# BUCK-BOOST_DC-DC_old.net
KiCad netlist of a schematic drawn in Altium Designer
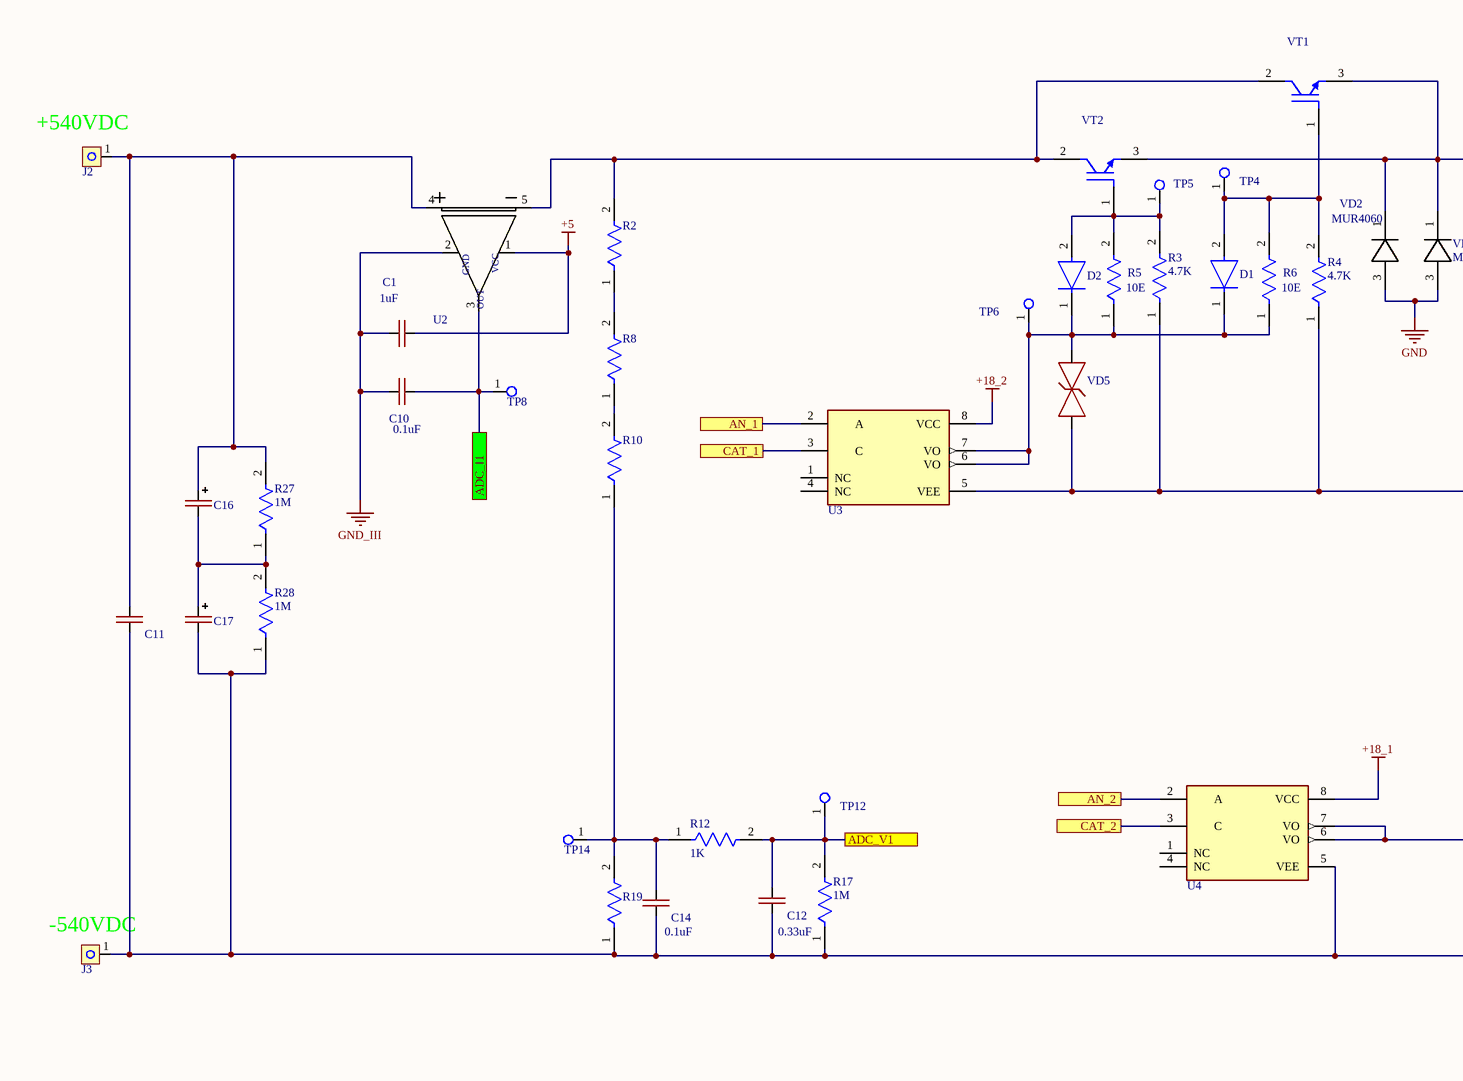
[diagram p0: BUCK-BOOST_DC-DC_old.SchDoc, top left]
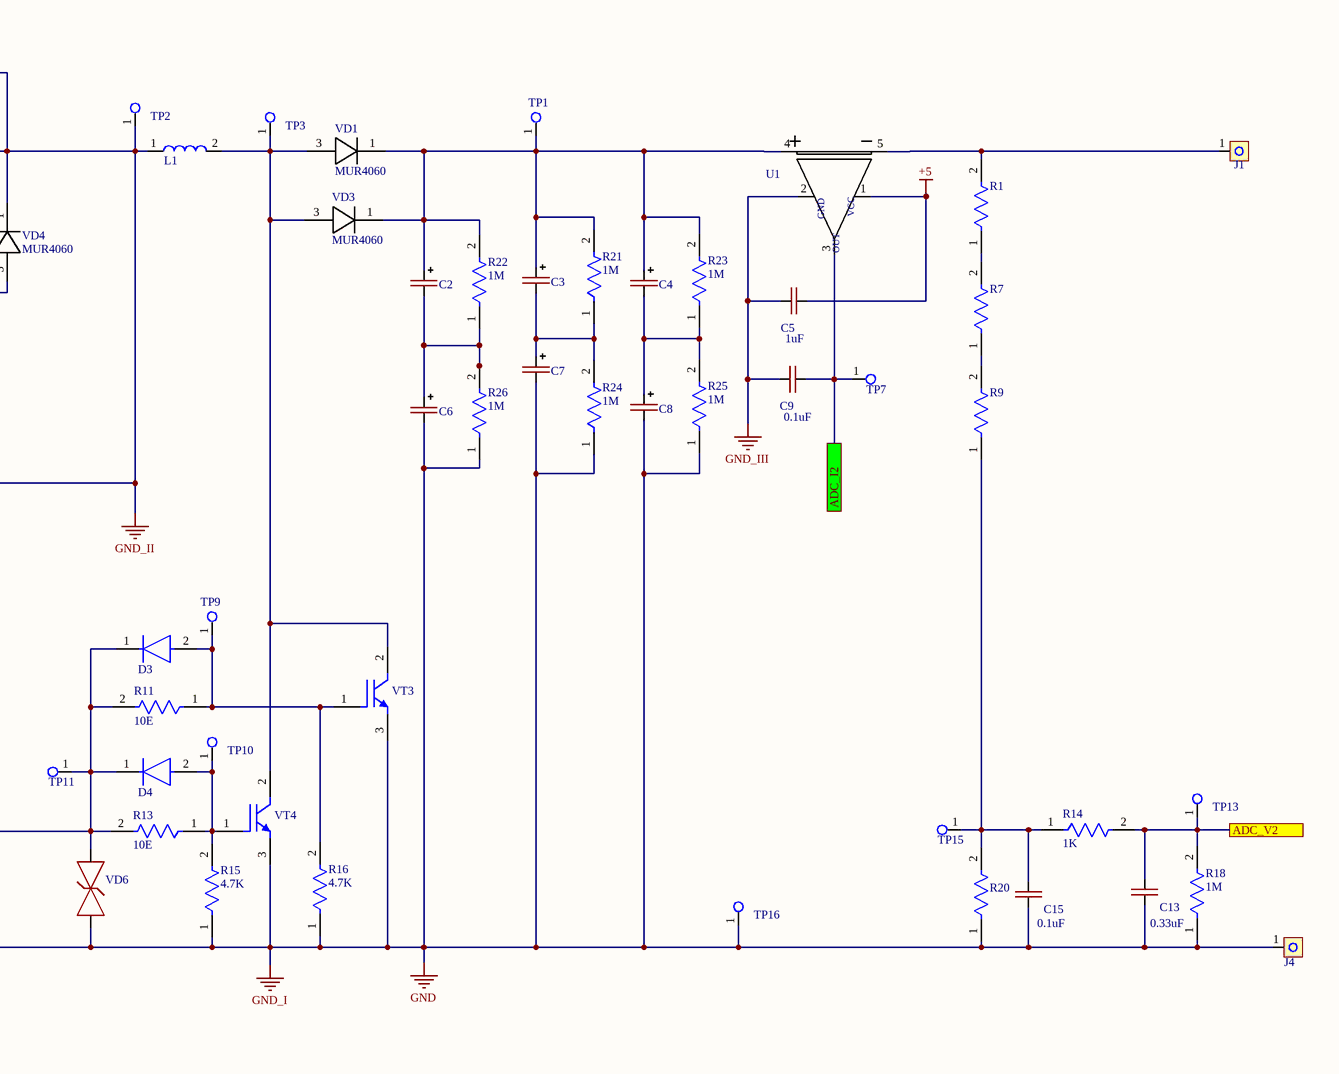
[diagram p1: BUCK-BOOST_DC-DC_old.SchDoc, top right]
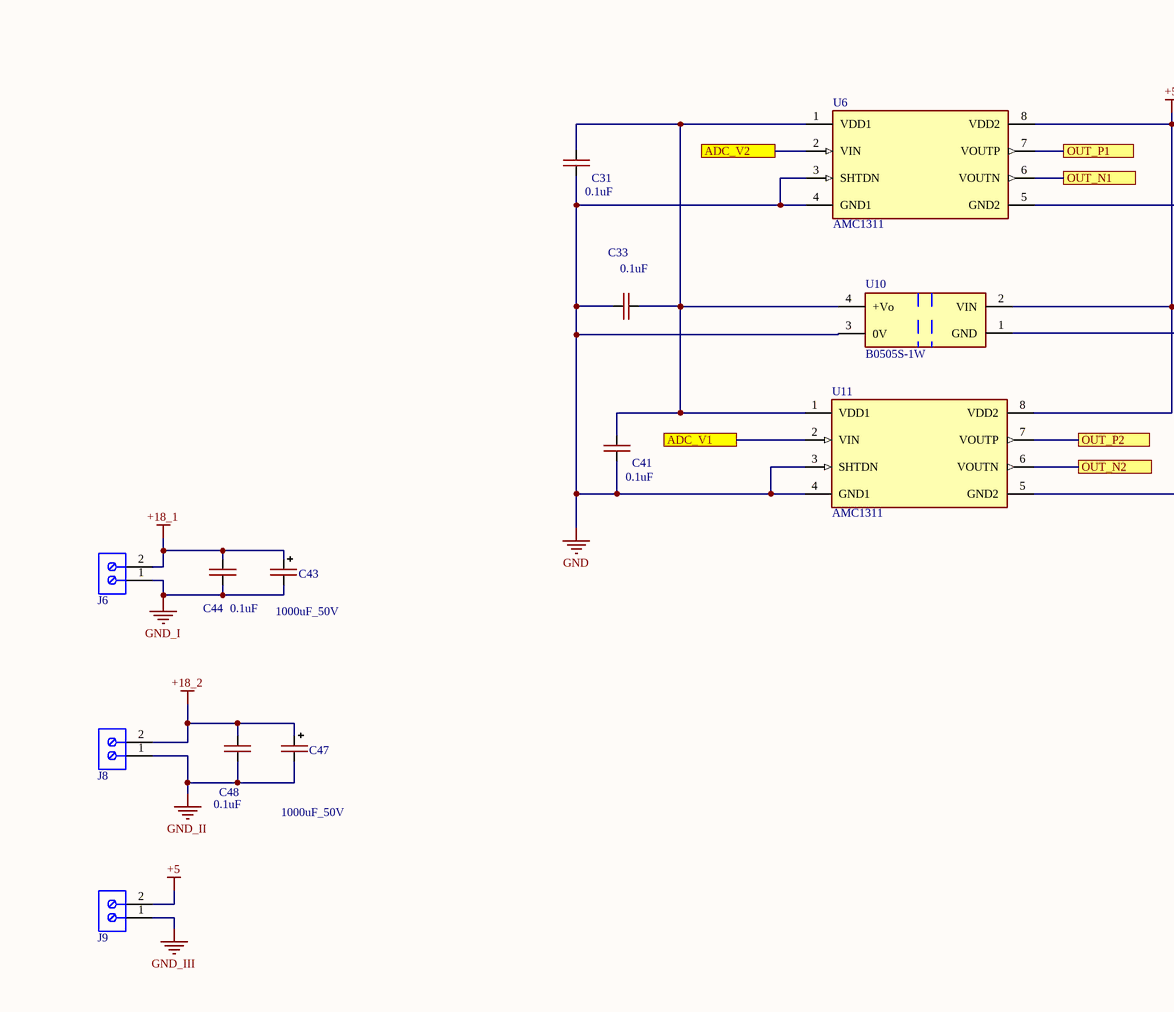
[diagram p2: BUCK-BOOST_DC-DC_old.SchDoc, bottom left]
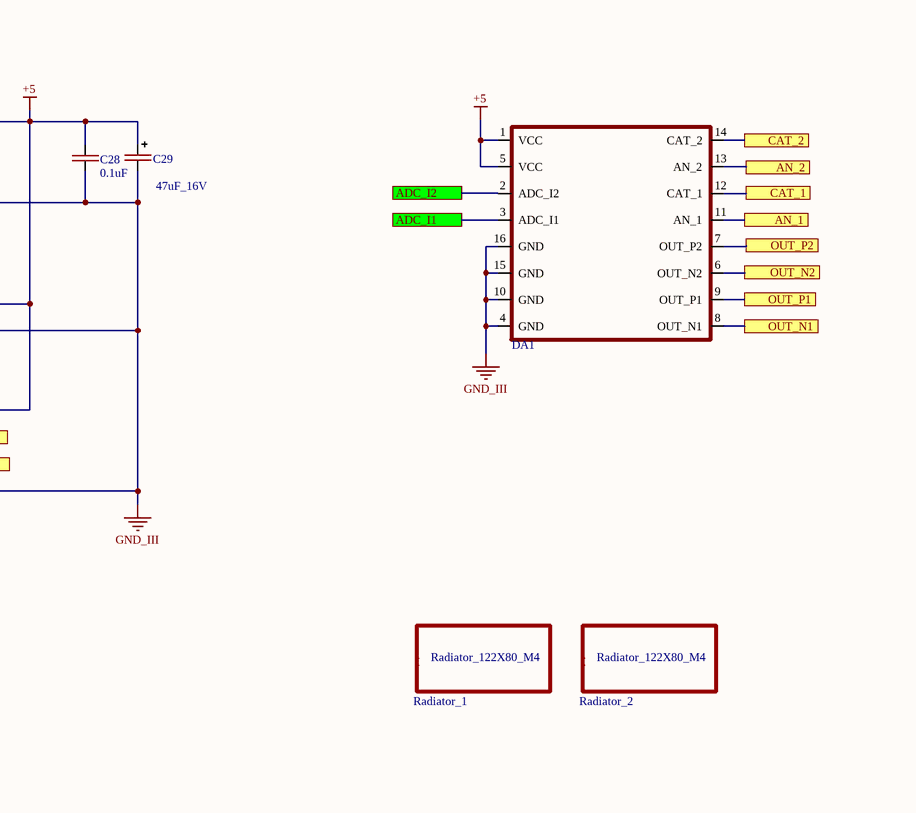
[diagram p3: BUCK-BOOST_DC-DC_old.SchDoc, bottom right]

(export (version "E")
  (design (tool "Eeschema 10.0.6"))
  (components
    (comp (ref "C1")
      (value "1uF")
      (footprint "CAP-0805")
      (libsource (lib "PASSIVE_COMPONENTS") (part "CAP-NON-POLAR"))
    )
    (comp (ref "C2")
      (value "CAP-POLAR")
      (footprint "CAP 100uF_500V 22x40mm")
      (libsource (lib "PASSIVE_COMPONENTS") (part "CAP-POLAR"))
    )
    (comp (ref "C3")
      (value "CAP-POLAR")
      (footprint "CAP 100uF_500V 22x40mm")
      (libsource (lib "PASSIVE_COMPONENTS") (part "CAP-POLAR"))
    )
    (comp (ref "C4")
      (value "CAP-POLAR")
      (footprint "CAP 100uF_500V 22x40mm")
      (libsource (lib "PASSIVE_COMPONENTS") (part "CAP-POLAR"))
    )
    (comp (ref "C5")
      (value "1uF")
      (footprint "CAP-0805")
      (libsource (lib "PASSIVE_COMPONENTS") (part "CAP-NON-POLAR"))
    )
    (comp (ref "C6")
      (value "CAP-POLAR")
      (footprint "CAP 100uF_500V 22x40mm")
      (libsource (lib "PASSIVE_COMPONENTS") (part "CAP-POLAR"))
    )
    (comp (ref "C7")
      (value "CAP-POLAR")
      (footprint "CAP 100uF_500V 22x40mm")
      (libsource (lib "PASSIVE_COMPONENTS") (part "CAP-POLAR"))
    )
    (comp (ref "C8")
      (value "CAP-POLAR")
      (footprint "CAP 100uF_500V 22x40mm")
      (libsource (lib "PASSIVE_COMPONENTS") (part "CAP-POLAR"))
    )
    (comp (ref "C9")
      (value "0.1uF")
      (footprint "CAP-0805")
      (libsource (lib "PASSIVE_COMPONENTS") (part "CAP-NON-POLAR"))
    )
    (comp (ref "C10")
      (value "0.1uF")
      (footprint "CAP-0805")
      (libsource (lib "PASSIVE_COMPONENTS") (part "CAP-NON-POLAR"))
    )
    (comp (ref "C11")
      (value "CAP-NON-POLAR")
      (footprint "CAP_4.7uF_630V")
      (libsource (lib "PASSIVE_COMPONENTS") (part "CAP-NON-POLAR"))
    )
    (comp (ref "C12")
      (value "0.33uF")
      (footprint "CAP-0805")
      (libsource (lib "PASSIVE_COMPONENTS") (part "CAP-NON-POLAR"))
    )
    (comp (ref "C13")
      (value "0.33uF")
      (footprint "CAP-0805")
      (libsource (lib "PASSIVE_COMPONENTS") (part "CAP-NON-POLAR"))
    )
    (comp (ref "C14")
      (value "0.1uF")
      (footprint "CAP-0805")
      (libsource (lib "PASSIVE_COMPONENTS") (part "CAP-NON-POLAR"))
    )
    (comp (ref "C15")
      (value "0.1uF")
      (footprint "CAP-0805")
      (libsource (lib "PASSIVE_COMPONENTS") (part "CAP-NON-POLAR"))
    )
    (comp (ref "C16")
      (value "CAP-POLAR")
      (footprint "CAP_POL_36X60")
      (libsource (lib "PASSIVE_COMPONENTS") (part "CAP-POLAR"))
    )
    (comp (ref "C17")
      (value "CAP-POLAR")
      (footprint "CAP_POL_36X60")
      (libsource (lib "PASSIVE_COMPONENTS") (part "CAP-POLAR"))
    )
    (comp (ref "C28")
      (value "0.1uF")
      (footprint "CAP-0805")
      (libsource (lib "PASSIVE_COMPONENTS") (part "CAP-NON-POLAR"))
    )
    (comp (ref "C29")
      (value "47uF_16V")
      (footprint "CAP-TAN-D")
      (libsource (lib "PASSIVE_COMPONENTS") (part "CAP-POLAR"))
    )
    (comp (ref "C31")
      (value "0.1uF")
      (footprint "CAP-0805")
      (libsource (lib "PASSIVE_COMPONENTS") (part "CAP-NON-POLAR"))
    )
    (comp (ref "C33")
      (value "0.1uF")
      (footprint "CAP-0805")
      (libsource (lib "PASSIVE_COMPONENTS") (part "CAP-NON-POLAR"))
    )
    (comp (ref "C41")
      (value "0.1uF")
      (footprint "CAP-0805")
      (libsource (lib "PASSIVE_COMPONENTS") (part "CAP-NON-POLAR"))
    )
    (comp (ref "C43")
      (value "1000uF_50V")
      (footprint "CAPPOL-16x25")
      (libsource (lib "PASSIVE_COMPONENTS") (part "CAP-POLAR"))
    )
    (comp (ref "C44")
      (value "0.1uF")
      (footprint "CAP-0805")
      (libsource (lib "PASSIVE_COMPONENTS") (part "CAP-NON-POLAR"))
    )
    (comp (ref "C47")
      (value "1000uF_50V")
      (footprint "CAPPOL-16x25")
      (libsource (lib "PASSIVE_COMPONENTS") (part "CAP-POLAR"))
    )
    (comp (ref "C48")
      (value "0.1uF")
      (footprint "CAP-0805")
      (libsource (lib "PASSIVE_COMPONENTS") (part "CAP-NON-POLAR"))
    )
    (comp (ref "D1") (value "US1G") (footprint "DO-214AA") (libsource (lib "Diodes") (part "US1G")))
    (comp (ref "D2") (value "US1G") (footprint "DO-214AA") (libsource (lib "Diodes") (part "US1G")))
    (comp (ref "D3") (value "US1G") (footprint "DO-214AA") (libsource (lib "Diodes") (part "US1G")))
    (comp (ref "D4") (value "US1G") (footprint "DO-214AA") (libsource (lib "Diodes") (part "US1G")))
    (comp (ref "DA1")
      (value "BOARD_PFC")
      (footprint "BOARD_PFC")
      (libsource (lib "BOARD_PFC") (part "BOARD_PFC"))
    )
    (comp (ref "J1")
      (value "MG_136_HT")
      (footprint "Conn_MEIGAN_MG136HT")
      (libsource (lib "Connectors") (part "Connector_MEIGAN_MG136HT"))
    )
    (comp (ref "J2")
      (value "MG_136_HT")
      (footprint "Conn_MEIGAN_MG136HT")
      (libsource (lib "") (part "Connector_MEIGAN_MG136HT_1"))
    )
    (comp (ref "J3")
      (value "MG_136_HT")
      (footprint "Conn_MEIGAN_MG136HT")
      (libsource (lib "") (part "Connector_MEIGAN_MG136HT_1"))
    )
    (comp (ref "J4")
      (value "MG_136_HT")
      (footprint "Conn_MEIGAN_MG136HT")
      (libsource (lib "Connectors") (part "Connector_MEIGAN_MG136HT"))
    )
    (comp (ref "J6")
      (value "691102710002")
      (footprint "691102710002")
      (description "WR-TBL Series 102 Horizontal Entry Modular, THT, pitch 5mm, 2p")
      (fields (field (name "MANUFACTURER") "Wurth Elektronik"))
      (libsource (lib "Altium_WR-TBL (rev23f)") (part "691102710002"))
    )
    (comp (ref "J8")
      (value "691102710002")
      (footprint "691102710002")
      (description "WR-TBL Series 102 Horizontal Entry Modular, THT, pitch 5mm, 2p")
      (fields (field (name "MANUFACTURER") "Wurth Elektronik"))
      (libsource (lib "Altium_WR-TBL (rev23f)") (part "691102710002"))
    )
    (comp (ref "J9")
      (value "691102710002")
      (footprint "691102710002")
      (description "WR-TBL Series 102 Horizontal Entry Modular, THT, pitch 5mm, 2p")
      (fields (field (name "MANUFACTURER") "Wurth Elektronik"))
      (libsource (lib "Altium_WR-TBL (rev23f)") (part "691102710002"))
    )
    (comp (ref "L1") (value "Coil") (footprint "30A_10uH") (libsource (lib "Transformers") (part "Coil")))
    (comp (ref "R1")
      (value "~")
      (footprint "RES-2512")
      (libsource (lib "PASSIVE_COMPONENTS") (part "RES-CONST"))
    )
    (comp (ref "R2")
      (value "~")
      (footprint "RES-2512")
      (libsource (lib "PASSIVE_COMPONENTS") (part "RES-CONST"))
    )
    (comp (ref "R3")
      (value "4.7K")
      (footprint "RES-0805")
      (libsource (lib "PASSIVE_COMPONENTS") (part "RES-CONST"))
    )
    (comp (ref "R4")
      (value "4.7K")
      (footprint "RES-0805")
      (libsource (lib "PASSIVE_COMPONENTS") (part "RES-CONST"))
    )
    (comp (ref "R5")
      (value "10E")
      (footprint "RES_SMD_1210_IPC_A")
      (libsource (lib "PASSIVE_COMPONENTS") (part "RES_1210"))
    )
    (comp (ref "R6")
      (value "10E")
      (footprint "RES_SMD_1210_IPC_A")
      (libsource (lib "PASSIVE_COMPONENTS") (part "RES_1210"))
    )
    (comp (ref "R7")
      (value "~")
      (footprint "RES-2512")
      (libsource (lib "PASSIVE_COMPONENTS") (part "RES-CONST"))
    )
    (comp (ref "R8")
      (value "~")
      (footprint "RES-2512")
      (libsource (lib "PASSIVE_COMPONENTS") (part "RES-CONST"))
    )
    (comp (ref "R9")
      (value "~")
      (footprint "RES-2512")
      (libsource (lib "PASSIVE_COMPONENTS") (part "RES-CONST"))
    )
    (comp (ref "R10")
      (value "~")
      (footprint "RES-2512")
      (libsource (lib "PASSIVE_COMPONENTS") (part "RES-CONST"))
    )
    (comp (ref "R11")
      (value "10E")
      (footprint "RES_SMD_1210_IPC_A")
      (libsource (lib "PASSIVE_COMPONENTS") (part "RES_1210"))
    )
    (comp (ref "R12")
      (value "1K")
      (footprint "RES-0805")
      (libsource (lib "PASSIVE_COMPONENTS") (part "RES-CONST"))
    )
    (comp (ref "R13")
      (value "10E")
      (footprint "RES_SMD_1210_IPC_A")
      (libsource (lib "PASSIVE_COMPONENTS") (part "RES_1210"))
    )
    (comp (ref "R14")
      (value "1K")
      (footprint "RES-0805")
      (libsource (lib "PASSIVE_COMPONENTS") (part "RES-CONST"))
    )
    (comp (ref "R15")
      (value "4.7K")
      (footprint "RES-0805")
      (libsource (lib "PASSIVE_COMPONENTS") (part "RES-CONST"))
    )
    (comp (ref "R16")
      (value "4.7K")
      (footprint "RES-0805")
      (libsource (lib "PASSIVE_COMPONENTS") (part "RES-CONST"))
    )
    (comp (ref "R17")
      (value "1M")
      (footprint "RES-0805")
      (libsource (lib "PASSIVE_COMPONENTS") (part "RES-CONST"))
    )
    (comp (ref "R18")
      (value "1M")
      (footprint "RES-0805")
      (libsource (lib "PASSIVE_COMPONENTS") (part "RES-CONST"))
    )
    (comp (ref "R19")
      (value "RES_1210")
      (footprint "RES_SMD_1210_IPC_B")
      (libsource (lib "PASSIVE_COMPONENTS") (part "RES_1210"))
    )
    (comp (ref "R20")
      (value "RES_1210")
      (footprint "RES_SMD_1210_IPC_B")
      (libsource (lib "PASSIVE_COMPONENTS") (part "RES_1210"))
    )
    (comp (ref "R21")
      (value "1M")
      (footprint "RES-2512")
      (description "4.7K")
      (libsource (lib "PASSIVE_COMPONENTS") (part "RES-CONST"))
    )
    (comp (ref "R22")
      (value "1M")
      (footprint "RES-2512")
      (description "4.7K")
      (libsource (lib "PASSIVE_COMPONENTS") (part "RES-CONST"))
    )
    (comp (ref "R23")
      (value "1M")
      (footprint "RES-2512")
      (description "4.7K")
      (libsource (lib "PASSIVE_COMPONENTS") (part "RES-CONST"))
    )
    (comp (ref "R24")
      (value "1M")
      (footprint "RES-2512")
      (description "4.7K")
      (libsource (lib "PASSIVE_COMPONENTS") (part "RES-CONST"))
    )
    (comp (ref "R25")
      (value "1M")
      (footprint "RES-2512")
      (description "4.7K")
      (libsource (lib "PASSIVE_COMPONENTS") (part "RES-CONST"))
    )
    (comp (ref "R26")
      (value "1M")
      (footprint "RES-2512")
      (description "4.7K")
      (libsource (lib "PASSIVE_COMPONENTS") (part "RES-CONST"))
    )
    (comp (ref "R27")
      (value "1M")
      (footprint "RES-2512")
      (description "4.7K")
      (libsource (lib "PASSIVE_COMPONENTS") (part "RES-CONST"))
    )
    (comp (ref "R28")
      (value "1M")
      (footprint "RES-2512")
      (description "4.7K")
      (libsource (lib "PASSIVE_COMPONENTS") (part "RES-CONST"))
    )
    (comp (ref "Radiator_1")
      (value "Radiator_122X80_M4")
      (footprint "Radiator_122X80_M4")
      (libsource (lib "Radiator_122X80_M4") (part "Radiator_122X80_M4"))
    )
    (comp (ref "Radiator_2")
      (value "Radiator_122X80_M4")
      (footprint "Radiator_122X80_M4")
      (libsource (lib "Radiator_122X80_M4") (part "Radiator_122X80_M4"))
    )
    (comp (ref "TP1")
      (value "Test_Point_PCB")
      (footprint "Test_Point")
      (description "Test_Point")
      (libsource (lib "Connectors") (part "TP_PCB?"))
    )
    (comp (ref "TP2")
      (value "Test_Point_PCB")
      (footprint "Test_Point")
      (description "Test_Point")
      (libsource (lib "Connectors") (part "TP_PCB?"))
    )
    (comp (ref "TP3")
      (value "Test_Point_PCB")
      (footprint "Test_Point")
      (description "Test_Point")
      (libsource (lib "Connectors") (part "TP_PCB?"))
    )
    (comp (ref "TP4")
      (value "Test_Point_PCB")
      (footprint "Test_Point")
      (description "Test_Point")
      (libsource (lib "Connectors") (part "TP_PCB?"))
    )
    (comp (ref "TP5")
      (value "Test_Point_PCB")
      (footprint "Test_Point")
      (description "Test_Point")
      (libsource (lib "Connectors") (part "TP_PCB?"))
    )
    (comp (ref "TP6")
      (value "Test_Point_PCB")
      (footprint "Test_Point")
      (description "Test_Point")
      (libsource (lib "Connectors") (part "TP_PCB?"))
    )
    (comp (ref "TP7")
      (value "Test_Point_PCB")
      (footprint "Test_Point")
      (description "Test_Point")
      (libsource (lib "Connectors") (part "TP_PCB?"))
    )
    (comp (ref "TP8")
      (value "Test_Point_PCB")
      (footprint "Test_Point")
      (description "Test_Point")
      (libsource (lib "Connectors") (part "TP_PCB?"))
    )
    (comp (ref "TP9")
      (value "Test_Point_PCB")
      (footprint "Test_Point")
      (description "Test_Point")
      (libsource (lib "Connectors") (part "TP_PCB?"))
    )
    (comp (ref "TP10")
      (value "Test_Point_PCB")
      (footprint "Test_Point")
      (description "Test_Point")
      (libsource (lib "Connectors") (part "TP_PCB?"))
    )
    (comp (ref "TP11")
      (value "Test_Point_PCB")
      (footprint "Test_Point")
      (description "Test_Point")
      (libsource (lib "Connectors") (part "TP_PCB?"))
    )
    (comp (ref "TP12")
      (value "Test_Point_PCB")
      (footprint "Test_Point")
      (description "Test_Point")
      (libsource (lib "Connectors") (part "TP_PCB?"))
    )
    (comp (ref "TP13")
      (value "Test_Point_PCB")
      (footprint "Test_Point")
      (description "Test_Point")
      (libsource (lib "Connectors") (part "TP_PCB?"))
    )
    (comp (ref "TP14")
      (value "Test_Point_PCB")
      (footprint "Test_Point")
      (description "Test_Point")
      (libsource (lib "Connectors") (part "TP_PCB?"))
    )
    (comp (ref "TP15")
      (value "Test_Point_PCB")
      (footprint "Test_Point")
      (description "Test_Point")
      (libsource (lib "Connectors") (part "TP_PCB?"))
    )
    (comp (ref "TP16")
      (value "Test_Point_PCB")
      (footprint "Test_Point")
      (description "Test_Point")
      (libsource (lib "Connectors") (part "TP_PCB?"))
    )
    (comp (ref "U1")
      (value "ACS758")
      (footprint "ACS758-100")
      (libsource (lib "Integrated_Circuts") (part "ACS758"))
    )
    (comp (ref "U2")
      (value "ACS758")
      (footprint "ACS758-100")
      (libsource (lib "Integrated_Circuts") (part "ACS758"))
    )
    (comp (ref "U3")
      (value "HCPL-3120")
      (footprint "HCPL-3120")
      (libsource (lib "Integrated_Circuts") (part "HCPL-3120"))
    )
    (comp (ref "U4")
      (value "HCPL-3120")
      (footprint "HCPL-3120")
      (libsource (lib "Integrated_Circuts") (part "HCPL-3120"))
    )
    (comp (ref "U6")
      (value "AMC1311")
      (footprint "FP-DWV0008A-MFG")
      (libsource (lib "Integrated_Circuts") (part "AMC1311"))
    )
    (comp (ref "U10")
      (value "B0505S-1W")
      (footprint "B0505S-1W")
      (libsource (lib "Integrated_Circuts") (part "B0505S-1W"))
    )
    (comp (ref "U11")
      (value "AMC1311")
      (footprint "FP-DWV0008A-MFG")
      (libsource (lib "Integrated_Circuts") (part "AMC1311"))
    )
    (comp (ref "VD1") (value "MUR4060") (footprint "TO-247-2") (libsource (lib "Diodes") (part "MUR4060")))
    (comp (ref "VD2") (value "MUR4060") (footprint "TO-247-2") (libsource (lib "Diodes") (part "MUR4060")))
    (comp (ref "VD3") (value "MUR4060") (footprint "TO-247-2") (libsource (lib "Diodes") (part "MUR4060")))
    (comp (ref "VD4") (value "MUR4060") (footprint "TO-247-2") (libsource (lib "Diodes") (part "MUR4060")))
    (comp (ref "VD5")
      (value "Suppressor")
      (footprint "DO-214AA")
      (libsource (lib "Diodes") (part "Suppressor"))
    )
    (comp (ref "VD6")
      (value "Suppressor")
      (footprint "DO-214AA")
      (libsource (lib "Diodes") (part "Suppressor"))
    )
    (comp (ref "VT1")
      (value "IGBT 60N120T")
      (footprint "TO-264-3")
      (description "IGBT 60N120T TO-264-3")
      (libsource (lib "Transistors") (part "IGBT 60N120T"))
    )
    (comp (ref "VT2")
      (value "IGBT 60N120T")
      (footprint "TO-264-3")
      (description "IGBT 60N120T TO-264-3")
      (libsource (lib "Transistors") (part "IGBT 60N120T"))
    )
    (comp (ref "VT3")
      (value "IGBT 60N120T")
      (footprint "TO-264-3")
      (description "IGBT 60N120T TO-264-3")
      (libsource (lib "Transistors") (part "IGBT 60N120T"))
    )
    (comp (ref "VT4")
      (value "IGBT 60N120T")
      (footprint "TO-264-3")
      (description "IGBT 60N120T TO-264-3")
      (libsource (lib "Transistors") (part "IGBT 60N120T"))
    )
  )
  (nets
    (net (code "1") (name "+5") (class "Default")
      (node (ref "C1") (pin "2") (pinfunction "2_2") (pintype "passive"))
      (node (ref "C28") (pin "1") (pinfunction "1_1") (pintype "passive"))
      (node (ref "C29") (pin "1") (pinfunction "+_1") (pintype "passive"))
      (node (ref "C5") (pin "2") (pinfunction "2_2") (pintype "passive"))
      (node (ref "DA1") (pin "1") (pinfunction "VCC_1") (pintype "passive"))
      (node (ref "DA1") (pin "5") (pinfunction "VCC_5") (pintype "passive"))
      (node (ref "J9") (pin "2") (pinfunction "2_2") (pintype "passive"))
      (node (ref "U1") (pin "1") (pinfunction "+VCC_1") (pintype "passive"))
      (node (ref "U10") (pin "2") (pinfunction "VIN_2") (pintype "power_in"))
      (node (ref "U11") (pin "8") (pinfunction "VDD2_8") (pintype "power_in"))
      (node (ref "U2") (pin "1") (pinfunction "+VCC_1") (pintype "passive"))
      (node (ref "U6") (pin "8") (pinfunction "VDD2_8") (pintype "power_in"))
    )
    (net (code "2") (name "+18_1") (class "Default")
      (node (ref "C43") (pin "1") (pinfunction "+_1") (pintype "passive"))
      (node (ref "C44") (pin "2") (pinfunction "2_2") (pintype "passive"))
      (node (ref "J6") (pin "2") (pinfunction "2_2") (pintype "passive"))
      (node (ref "U4") (pin "8") (pinfunction "VCC_8") (pintype "power_in"))
    )
    (net (code "3") (name "+18_2") (class "Default")
      (node (ref "C47") (pin "1") (pinfunction "+_1") (pintype "passive"))
      (node (ref "C48") (pin "2") (pinfunction "2_2") (pintype "passive"))
      (node (ref "J8") (pin "2") (pinfunction "2_2") (pintype "passive"))
      (node (ref "U3") (pin "8") (pinfunction "VCC_8") (pintype "power_in"))
    )
    (net (code "4") (name "/ADC_I1") (class "Default")
      (node (ref "C10") (pin "2") (pinfunction "2_2") (pintype "passive"))
      (node (ref "DA1") (pin "3") (pinfunction "ADC_I1_3") (pintype "passive"))
      (node (ref "TP8") (pin "1") (pinfunction "G9_1") (pintype "passive"))
      (node (ref "U2") (pin "3") (pinfunction "OUT_3") (pintype "passive"))
    )
    (net (code "5") (name "/ADC_I2") (class "Default")
      (node (ref "C9") (pin "2") (pinfunction "2_2") (pintype "passive"))
      (node (ref "DA1") (pin "2") (pinfunction "ADC_I2_2") (pintype "passive"))
      (node (ref "TP7") (pin "1") (pinfunction "G9_1") (pintype "passive"))
      (node (ref "U1") (pin "3") (pinfunction "OUT_3") (pintype "passive"))
    )
    (net (code "6") (name "/ADC_V1") (class "Default")
      (node (ref "C12") (pin "2") (pinfunction "2_2") (pintype "passive"))
      (node (ref "R12") (pin "2") (pinfunction "2_2") (pintype "passive"))
      (node (ref "R17") (pin "2") (pinfunction "2_2") (pintype "passive"))
      (node (ref "TP12") (pin "1") (pinfunction "G9_1") (pintype "passive"))
      (node (ref "U11") (pin "2") (pinfunction "VIN_2") (pintype "input"))
    )
    (net (code "7") (name "/ADC_V2") (class "Default")
      (node (ref "C13") (pin "2") (pinfunction "2_2") (pintype "passive"))
      (node (ref "R14") (pin "2") (pinfunction "2_2") (pintype "passive"))
      (node (ref "R18") (pin "2") (pinfunction "2_2") (pintype "passive"))
      (node (ref "TP13") (pin "1") (pinfunction "G9_1") (pintype "passive"))
      (node (ref "U6") (pin "2") (pinfunction "VIN_2") (pintype "input"))
    )
    (net (code "8") (name "/AN_1") (class "Default")
      (node (ref "DA1") (pin "11") (pinfunction "AN_1_11") (pintype "passive"))
      (node (ref "U3") (pin "2") (pinfunction "A_2") (pintype "passive"))
    )
    (net (code "9") (name "/AN_2") (class "Default")
      (node (ref "DA1") (pin "13") (pinfunction "AN_2_13") (pintype "passive"))
      (node (ref "U4") (pin "2") (pinfunction "A_2") (pintype "passive"))
    )
    (net (code "10") (name "/CAT_1") (class "Default")
      (node (ref "DA1") (pin "12") (pinfunction "CAT_1_12") (pintype "passive"))
      (node (ref "U3") (pin "3") (pinfunction "C_3") (pintype "passive"))
    )
    (net (code "11") (name "/CAT_2") (class "Default")
      (node (ref "DA1") (pin "14") (pinfunction "CAT_2_14") (pintype "passive"))
      (node (ref "U4") (pin "3") (pinfunction "C_3") (pintype "passive"))
    )
    (net (code "12") (name "/OUT_N1") (class "Default")
      (node (ref "DA1") (pin "8") (pinfunction "OUT_N1_8") (pintype "passive"))
      (node (ref "U6") (pin "6") (pinfunction "VOUTN_6") (pintype "output"))
    )
    (net (code "13") (name "/OUT_N2") (class "Default")
      (node (ref "DA1") (pin "6") (pinfunction "OUT_N2_6") (pintype "passive"))
      (node (ref "U11") (pin "6") (pinfunction "VOUTN_6") (pintype "output"))
    )
    (net (code "14") (name "/OUT_P1") (class "Default")
      (node (ref "DA1") (pin "9") (pinfunction "OUT_P1_9") (pintype "passive"))
      (node (ref "U6") (pin "7") (pinfunction "VOUTP_7") (pintype "output"))
    )
    (net (code "15") (name "/OUT_P2") (class "Default")
      (node (ref "DA1") (pin "7") (pinfunction "OUT_P2_7") (pintype "passive"))
      (node (ref "U11") (pin "7") (pinfunction "VOUTP_7") (pintype "output"))
    )
    (net (code "16") (name "GND") (class "Default")
      (node (ref "C11") (pin "1") (pinfunction "1_1") (pintype "passive"))
      (node (ref "C12") (pin "1") (pinfunction "1_1") (pintype "passive"))
      (node (ref "C13") (pin "1") (pinfunction "1_1") (pintype "passive"))
      (node (ref "C14") (pin "1") (pinfunction "1_1") (pintype "passive"))
      (node (ref "C15") (pin "1") (pinfunction "1_1") (pintype "passive"))
      (node (ref "C17") (pin "2") (pinfunction "-_2") (pintype "passive"))
      (node (ref "C31") (pin "1") (pinfunction "1_1") (pintype "passive"))
      (node (ref "C33") (pin "2") (pinfunction "2_2") (pintype "passive"))
      (node (ref "C41") (pin "1") (pinfunction "1_1") (pintype "passive"))
      (node (ref "C43") (pin "2") (pinfunction "-_2") (pintype "passive"))
      (node (ref "C44") (pin "1") (pinfunction "1_1") (pintype "passive"))
      (node (ref "C6") (pin "2") (pinfunction "-_2") (pintype "passive"))
      (node (ref "C7") (pin "2") (pinfunction "-_2") (pintype "passive"))
      (node (ref "C8") (pin "2") (pinfunction "-_2") (pintype "passive"))
      (node (ref "J3") (pin "1") (pinfunction "17_1") (pintype "passive"))
      (node (ref "J4") (pin "1") (pinfunction "17_1") (pintype "passive"))
      (node (ref "J6") (pin "1") (pinfunction "1_1") (pintype "passive"))
      (node (ref "R15") (pin "1") (pinfunction "1_1") (pintype "passive"))
      (node (ref "R16") (pin "1") (pinfunction "1_1") (pintype "passive"))
      (node (ref "R17") (pin "1") (pinfunction "1_1") (pintype "passive"))
      (node (ref "R18") (pin "1") (pinfunction "1_1") (pintype "passive"))
      (node (ref "R19") (pin "1") (pinfunction "1_1") (pintype "passive"))
      (node (ref "R20") (pin "1") (pinfunction "1_1") (pintype "passive"))
      (node (ref "R24") (pin "1") (pinfunction "1_1") (pintype "passive"))
      (node (ref "R25") (pin "1") (pinfunction "1_1") (pintype "passive"))
      (node (ref "R26") (pin "1") (pinfunction "1_1") (pintype "passive"))
      (node (ref "R28") (pin "1") (pinfunction "1_1") (pintype "passive"))
      (node (ref "TP16") (pin "1") (pinfunction "G9_1") (pintype "passive"))
      (node (ref "U10") (pin "3") (pinfunction "0V_3") (pintype "power_in"))
      (node (ref "U11") (pin "3") (pinfunction "SHTDN_3") (pintype "input"))
      (node (ref "U11") (pin "4") (pinfunction "GND1_4") (pintype "power_in"))
      (node (ref "U4") (pin "5") (pinfunction "VEE_5") (pintype "power_in"))
      (node (ref "U6") (pin "3") (pinfunction "SHTDN_3") (pintype "input"))
      (node (ref "U6") (pin "4") (pinfunction "GND1_4") (pintype "power_in"))
      (node (ref "VD2") (pin "3") (pinfunction "3_3") (pintype "passive"))
      (node (ref "VD4") (pin "3") (pinfunction "3_3") (pintype "passive"))
      (node (ref "VD6") (pin "1") (pinfunction "C_1") (pintype "passive"))
      (node (ref "VT3") (pin "3") (pinfunction "E_3") (pintype "passive"))
      (node (ref "VT4") (pin "3") (pinfunction "E_3") (pintype "passive"))
    )
    (net (code "17") (name "GND_II") (class "Default")
      (node (ref "C47") (pin "2") (pinfunction "-_2") (pintype "passive"))
      (node (ref "C48") (pin "1") (pinfunction "1_1") (pintype "passive"))
      (node (ref "J8") (pin "1") (pinfunction "1_1") (pintype "passive"))
      (node (ref "L1") (pin "1") (pinfunction "1_1") (pintype "passive"))
      (node (ref "R3") (pin "1") (pinfunction "1_1") (pintype "passive"))
      (node (ref "R4") (pin "1") (pinfunction "1_1") (pintype "passive"))
      (node (ref "TP2") (pin "1") (pinfunction "G9_1") (pintype "passive"))
      (node (ref "U3") (pin "5") (pinfunction "VEE_5") (pintype "power_in"))
      (node (ref "VD2") (pin "1") (pinfunction "1_1") (pintype "passive"))
      (node (ref "VD4") (pin "1") (pinfunction "1_1") (pintype "passive"))
      (node (ref "VD5") (pin "1") (pinfunction "C_1") (pintype "passive"))
      (node (ref "VT1") (pin "3") (pinfunction "E_3") (pintype "passive"))
      (node (ref "VT2") (pin "3") (pinfunction "E_3") (pintype "passive"))
    )
    (net (code "18") (name "GND_III") (class "Default")
      (node (ref "C1") (pin "1") (pinfunction "1_1") (pintype "passive"))
      (node (ref "C10") (pin "1") (pinfunction "1_1") (pintype "passive"))
      (node (ref "C28") (pin "2") (pinfunction "2_2") (pintype "passive"))
      (node (ref "C29") (pin "2") (pinfunction "-_2") (pintype "passive"))
      (node (ref "C5") (pin "1") (pinfunction "1_1") (pintype "passive"))
      (node (ref "C9") (pin "1") (pinfunction "1_1") (pintype "passive"))
      (node (ref "DA1") (pin "10") (pinfunction "GND_10") (pintype "passive"))
      (node (ref "DA1") (pin "15") (pinfunction "GND_15") (pintype "passive"))
      (node (ref "DA1") (pin "16") (pinfunction "GND_16") (pintype "passive"))
      (node (ref "DA1") (pin "4") (pinfunction "GND_4") (pintype "passive"))
      (node (ref "J9") (pin "1") (pinfunction "1_1") (pintype "passive"))
      (node (ref "U1") (pin "2") (pinfunction "GND_2") (pintype "passive"))
      (node (ref "U10") (pin "1") (pinfunction "GND_1") (pintype "power_in"))
      (node (ref "U11") (pin "5") (pinfunction "GND2_5") (pintype "power_in"))
      (node (ref "U2") (pin "2") (pinfunction "GND_2") (pintype "passive"))
      (node (ref "U6") (pin "5") (pinfunction "GND2_5") (pintype "power_in"))
    )
    (net (code "19") (name "Net-(C2-+)") (class "Default")
      (node (ref "C2") (pin "1") (pinfunction "+_1") (pintype "passive"))
      (node (ref "C3") (pin "1") (pinfunction "+_1") (pintype "passive"))
      (node (ref "C4") (pin "1") (pinfunction "+_1") (pintype "passive"))
      (node (ref "R21") (pin "2") (pinfunction "2_2") (pintype "passive"))
      (node (ref "R22") (pin "2") (pinfunction "2_2") (pintype "passive"))
      (node (ref "R23") (pin "2") (pinfunction "2_2") (pintype "passive"))
      (node (ref "TP1") (pin "1") (pinfunction "G9_1") (pintype "passive"))
      (node (ref "U1") (pin "4") (pinfunction "+IP_4") (pintype "passive"))
      (node (ref "VD1") (pin "1") (pinfunction "1_1") (pintype "passive"))
      (node (ref "VD3") (pin "1") (pinfunction "1_1") (pintype "passive"))
    )
    (net (code "20") (name "Net-(C2--)") (class "Default")
      (node (ref "C2") (pin "2") (pinfunction "-_2") (pintype "passive"))
      (node (ref "C6") (pin "1") (pinfunction "+_1") (pintype "passive"))
      (node (ref "R22") (pin "1") (pinfunction "1_1") (pintype "passive"))
      (node (ref "R26") (pin "2") (pinfunction "2_2") (pintype "passive"))
    )
    (net (code "21") (name "Net-(C3--)") (class "Default")
      (node (ref "C3") (pin "2") (pinfunction "-_2") (pintype "passive"))
      (node (ref "C7") (pin "1") (pinfunction "+_1") (pintype "passive"))
      (node (ref "R21") (pin "1") (pinfunction "1_1") (pintype "passive"))
      (node (ref "R24") (pin "2") (pinfunction "2_2") (pintype "passive"))
    )
    (net (code "22") (name "Net-(C4--)") (class "Default")
      (node (ref "C4") (pin "2") (pinfunction "-_2") (pintype "passive"))
      (node (ref "C8") (pin "1") (pinfunction "+_1") (pintype "passive"))
      (node (ref "R23") (pin "1") (pinfunction "1_1") (pintype "passive"))
      (node (ref "R25") (pin "2") (pinfunction "2_2") (pintype "passive"))
    )
    (net (code "23") (name "Net-(C16-+)") (class "Default")
      (node (ref "C11") (pin "2") (pinfunction "2_2") (pintype "passive"))
      (node (ref "C16") (pin "1") (pinfunction "+_1") (pintype "passive"))
      (node (ref "J2") (pin "1") (pinfunction "17_1") (pintype "passive"))
      (node (ref "R27") (pin "2") (pinfunction "2_2") (pintype "passive"))
      (node (ref "U2") (pin "4") (pinfunction "+IP_4") (pintype "passive"))
    )
    (net (code "24") (name "Net-(C16--)") (class "Default")
      (node (ref "C16") (pin "2") (pinfunction "-_2") (pintype "passive"))
      (node (ref "C17") (pin "1") (pinfunction "+_1") (pintype "passive"))
      (node (ref "R27") (pin "1") (pinfunction "1_1") (pintype "passive"))
      (node (ref "R28") (pin "2") (pinfunction "2_2") (pintype "passive"))
    )
    (net (code "25") (name "Net-(D1-A)") (class "Default")
      (node (ref "D1") (pin "2") (pinfunction "A_2") (pintype "passive"))
      (node (ref "R4") (pin "2") (pinfunction "2_2") (pintype "passive"))
      (node (ref "R6") (pin "2") (pinfunction "2_2") (pintype "passive"))
      (node (ref "TP4") (pin "1") (pinfunction "G9_1") (pintype "passive"))
      (node (ref "VT1") (pin "1") (pinfunction "G_1") (pintype "passive"))
    )
    (net (code "26") (name "Net-(D1-C)") (class "Default")
      (node (ref "D1") (pin "1") (pinfunction "C_1") (pintype "passive"))
      (node (ref "D2") (pin "1") (pinfunction "C_1") (pintype "passive"))
      (node (ref "R5") (pin "1") (pinfunction "1_1") (pintype "passive"))
      (node (ref "R6") (pin "1") (pinfunction "1_1") (pintype "passive"))
      (node (ref "TP6") (pin "1") (pinfunction "G9_1") (pintype "passive"))
      (node (ref "U3") (pin "6") (pinfunction "VO_6") (pintype "output"))
      (node (ref "U3") (pin "7") (pinfunction "VO_7") (pintype "output"))
      (node (ref "VD5") (pin "2") (pinfunction "A_2") (pintype "passive"))
    )
    (net (code "27") (name "Net-(D2-A)") (class "Default")
      (node (ref "D2") (pin "2") (pinfunction "A_2") (pintype "passive"))
      (node (ref "R3") (pin "2") (pinfunction "2_2") (pintype "passive"))
      (node (ref "R5") (pin "2") (pinfunction "2_2") (pintype "passive"))
      (node (ref "TP5") (pin "1") (pinfunction "G9_1") (pintype "passive"))
      (node (ref "VT2") (pin "1") (pinfunction "G_1") (pintype "passive"))
    )
    (net (code "28") (name "Net-(D3-A)") (class "Default")
      (node (ref "D3") (pin "2") (pinfunction "A_2") (pintype "passive"))
      (node (ref "R11") (pin "1") (pinfunction "1_1") (pintype "passive"))
      (node (ref "R16") (pin "2") (pinfunction "2_2") (pintype "passive"))
      (node (ref "TP9") (pin "1") (pinfunction "G9_1") (pintype "passive"))
      (node (ref "VT3") (pin "1") (pinfunction "G_1") (pintype "passive"))
    )
    (net (code "29") (name "Net-(D3-C)") (class "Default")
      (node (ref "D3") (pin "1") (pinfunction "C_1") (pintype "passive"))
      (node (ref "D4") (pin "1") (pinfunction "C_1") (pintype "passive"))
      (node (ref "R11") (pin "2") (pinfunction "2_2") (pintype "passive"))
      (node (ref "R13") (pin "2") (pinfunction "2_2") (pintype "passive"))
      (node (ref "TP11") (pin "1") (pinfunction "G9_1") (pintype "passive"))
      (node (ref "U4") (pin "6") (pinfunction "VO_6") (pintype "output"))
      (node (ref "U4") (pin "7") (pinfunction "VO_7") (pintype "output"))
      (node (ref "VD6") (pin "2") (pinfunction "A_2") (pintype "passive"))
    )
    (net (code "30") (name "Net-(D4-A)") (class "Default")
      (node (ref "D4") (pin "2") (pinfunction "A_2") (pintype "passive"))
      (node (ref "R13") (pin "1") (pinfunction "1_1") (pintype "passive"))
      (node (ref "R15") (pin "2") (pinfunction "2_2") (pintype "passive"))
      (node (ref "TP10") (pin "1") (pinfunction "G9_1") (pintype "passive"))
      (node (ref "VT4") (pin "1") (pinfunction "G_1") (pintype "passive"))
    )
    (net (code "31") (name "Net-(J1-17)") (class "Default")
      (node (ref "J1") (pin "1") (pinfunction "17_1") (pintype "passive"))
      (node (ref "R1") (pin "2") (pinfunction "2_2") (pintype "passive"))
      (node (ref "U1") (pin "5") (pinfunction "-IP_5") (pintype "passive"))
    )
    (net (code "32") (name "Net-(R1-Pad1)") (class "Default")
      (node (ref "R1") (pin "1") (pinfunction "1_1") (pintype "passive"))
      (node (ref "R7") (pin "2") (pinfunction "2_2") (pintype "passive"))
    )
    (net (code "33") (name "Net-(R2-Pad1)") (class "Default")
      (node (ref "R2") (pin "1") (pinfunction "1_1") (pintype "passive"))
      (node (ref "R8") (pin "2") (pinfunction "2_2") (pintype "passive"))
    )
    (net (code "34") (name "Net-(R7-Pad1)") (class "Default")
      (node (ref "R7") (pin "1") (pinfunction "1_1") (pintype "passive"))
      (node (ref "R9") (pin "2") (pinfunction "2_2") (pintype "passive"))
    )
    (net (code "35") (name "Net-(R10-Pad2)") (class "Default")
      (node (ref "R10") (pin "2") (pinfunction "2_2") (pintype "passive"))
      (node (ref "R8") (pin "1") (pinfunction "1_1") (pintype "passive"))
    )
    (net (code "36") (name "Net-(TP3-G9)") (class "Default")
      (node (ref "L1") (pin "2") (pinfunction "2_2") (pintype "passive"))
      (node (ref "TP3") (pin "1") (pinfunction "G9_1") (pintype "passive"))
      (node (ref "VD1") (pin "3") (pinfunction "3_3") (pintype "passive"))
      (node (ref "VD3") (pin "3") (pinfunction "3_3") (pintype "passive"))
      (node (ref "VT3") (pin "2") (pinfunction "C_2") (pintype "passive"))
      (node (ref "VT4") (pin "2") (pinfunction "C_2") (pintype "passive"))
    )
    (net (code "37") (name "Net-(TP14-G9)") (class "Default")
      (node (ref "C14") (pin "2") (pinfunction "2_2") (pintype "passive"))
      (node (ref "R10") (pin "1") (pinfunction "1_1") (pintype "passive"))
      (node (ref "R12") (pin "1") (pinfunction "1_1") (pintype "passive"))
      (node (ref "R19") (pin "2") (pinfunction "2_2") (pintype "passive"))
      (node (ref "TP14") (pin "1") (pinfunction "G9_1") (pintype "passive"))
    )
    (net (code "38") (name "Net-(TP15-G9)") (class "Default")
      (node (ref "C15") (pin "2") (pinfunction "2_2") (pintype "passive"))
      (node (ref "R14") (pin "1") (pinfunction "1_1") (pintype "passive"))
      (node (ref "R20") (pin "2") (pinfunction "2_2") (pintype "passive"))
      (node (ref "R9") (pin "1") (pinfunction "1_1") (pintype "passive"))
      (node (ref "TP15") (pin "1") (pinfunction "G9_1") (pintype "passive"))
    )
    (net (code "39") (name "Net-(U2--IP)") (class "Default")
      (node (ref "R2") (pin "2") (pinfunction "2_2") (pintype "passive"))
      (node (ref "U2") (pin "5") (pinfunction "-IP_5") (pintype "passive"))
      (node (ref "VT1") (pin "2") (pinfunction "C_2") (pintype "passive"))
      (node (ref "VT2") (pin "2") (pinfunction "C_2") (pintype "passive"))
    )
    (net (code "40") (name "Net-(U10-+Vo)") (class "Default")
      (node (ref "C31") (pin "2") (pinfunction "2_2") (pintype "passive"))
      (node (ref "C33") (pin "1") (pinfunction "1_1") (pintype "passive"))
      (node (ref "C41") (pin "2") (pinfunction "2_2") (pintype "passive"))
      (node (ref "U10") (pin "4") (pinfunction "+Vo_4") (pintype "power_in"))
      (node (ref "U11") (pin "1") (pinfunction "VDD1_1") (pintype "power_in"))
      (node (ref "U6") (pin "1") (pinfunction "VDD1_1") (pintype "power_in"))
    )
    (net (code "41") (name "unconnected-(U3-NC-Pad1)") (class "Default")
      (node (ref "U3") (pin "1") (pinfunction "NC_1") (pintype "passive"))
    )
    (net (code "42") (name "unconnected-(U3-NC-Pad4)") (class "Default")
      (node (ref "U3") (pin "4") (pinfunction "NC_4") (pintype "passive"))
    )
    (net (code "43") (name "unconnected-(U4-NC-Pad1)") (class "Default")
      (node (ref "U4") (pin "1") (pinfunction "NC_1") (pintype "passive"))
    )
    (net (code "44") (name "unconnected-(U4-NC-Pad4)") (class "Default")
      (node (ref "U4") (pin "4") (pinfunction "NC_4") (pintype "passive"))
    )
  )
)
